# SH_SW20_V1_0.net
KiCad netlist of a schematic drawn in Altium Designer
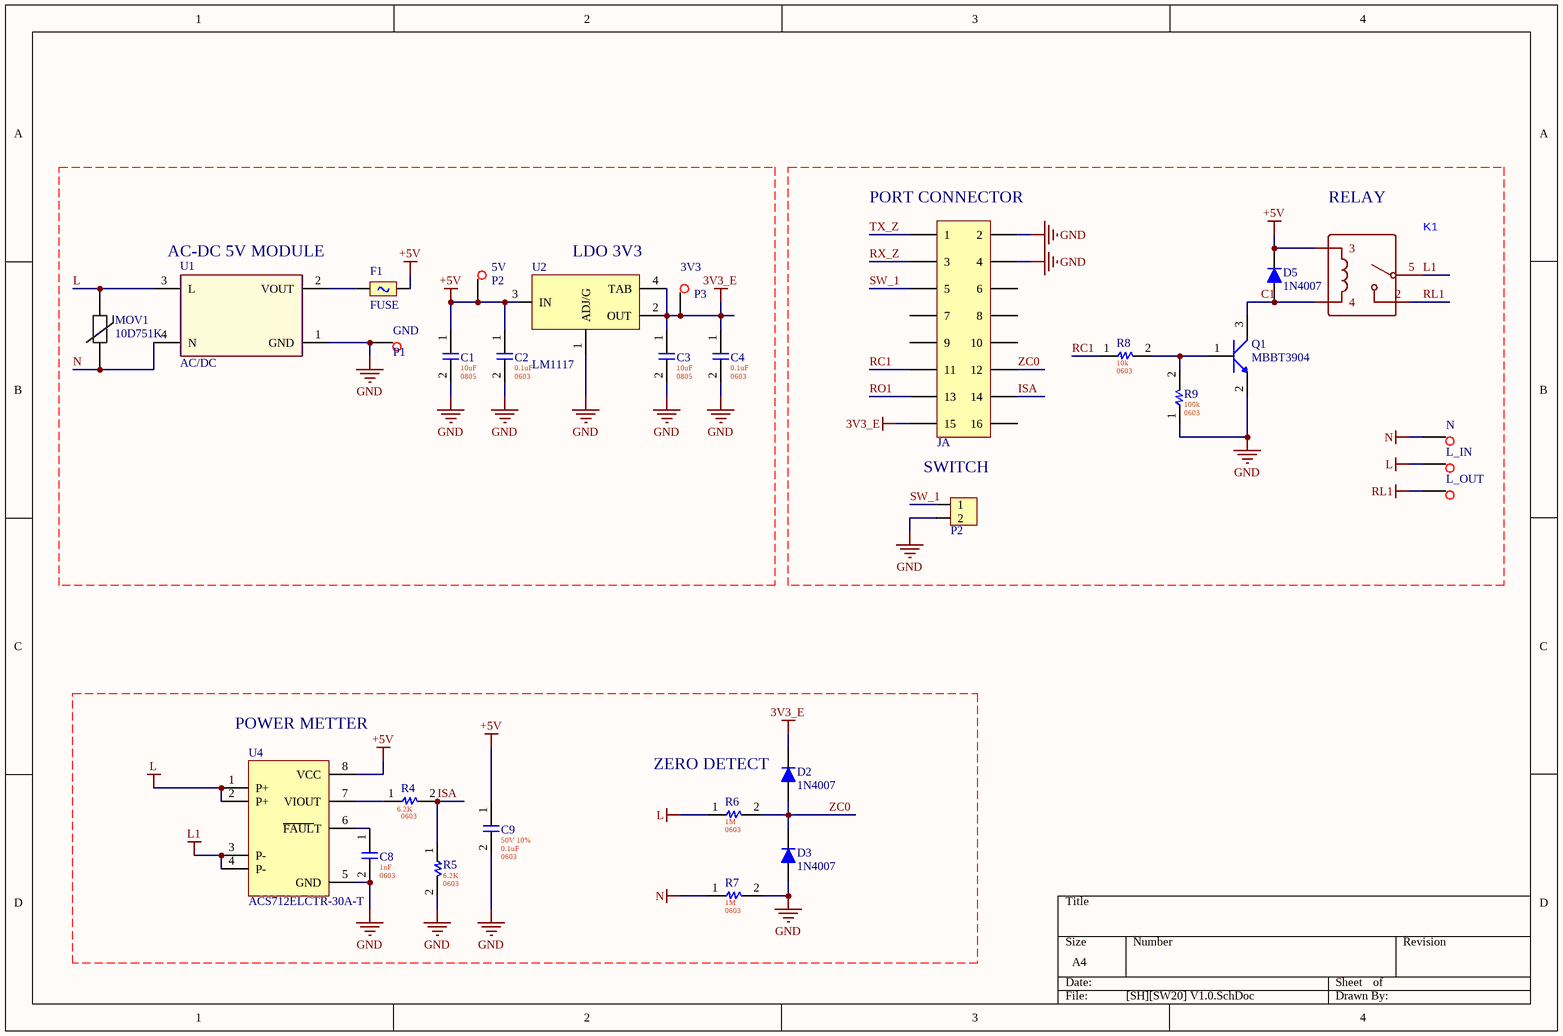
[diagram p0: [SH][SW20] V1.0.SchDoc]

(export (version "E")
  (design (tool "Eeschema 10.0.6"))
  (components
    (comp (ref "3V3") (value "P3") (footprint "TEXT_POINT") (libsource (lib "Kienlib") (part "P1")))
    (comp (ref "5V") (value "P2") (footprint "TEXT_POINT") (libsource (lib "Kienlib") (part "P1")))
    (comp (ref "C1")
      (value "10uF")
      (footprint "0805 C")
      (description "CAP CER 10uF 50V 10% 0805 SMD")
      (fields (field (name "FP") "0805") (field (name "CREATOR") "MMUOP"))
      (libsource (lib "Capacitor") (part "0805 10uF CER"))
    )
    (comp (ref "C2")
      (value "0.1uF")
      (footprint "0603 C")
      (description "CAP CER 0.1uF 50V 10% 0603 SMD")
      (fields (field (name "FP") "0603") (field (name "CREATOR") "MMUOP"))
      (libsource (lib "Capacitor") (part "0603 0.1uF CER"))
    )
    (comp (ref "C3")
      (value "10uF")
      (footprint "0805 C")
      (description "CAP CER 10uF 50V 10% 0805 SMD")
      (fields (field (name "FP") "0805") (field (name "CREATOR") "MMUOP"))
      (libsource (lib "Capacitor") (part "0805 10uF CER"))
    )
    (comp (ref "C4")
      (value "0.1uF")
      (footprint "0603 C")
      (description "CAP CER 0.1uF 50V 10% 0603 SMD")
      (fields (field (name "FP") "0603") (field (name "CREATOR") "MMUOP"))
      (libsource (lib "Capacitor") (part "0603 0.1uF CER"))
    )
    (comp (ref "C8")
      (value "1nF")
      (footprint "0603 C")
      (description "CAP CER 1nF 50V 10% 0603 SMD")
      (fields (field (name "FP") "0603") (field (name "CREATOR") "MMUOP"))
      (libsource (lib "Capacitor") (part "0603 1nF CER"))
    )
    (comp (ref "C9")
      (value "0.1uF")
      (footprint "0603 C")
      (description "CAP CER 0.1uF 50V 10% 0603 SMD")
      (fields
        (field (name "VOLTAGE + TOLE") "50V 10%")
        (field (name "FP") "0603")
        (field (name "CREATOR") "MMUOP")
      )
      (libsource (lib "Capacitor") (part "0603 0.1uF CER"))
    )
    (comp (ref "D2")
      (value "1N4007")
      (footprint "SOD-123")
      (libsource (lib "Kienlib") (part "Diode schottky"))
    )
    (comp (ref "D3")
      (value "1N4007")
      (footprint "SOD-123")
      (libsource (lib "Kienlib") (part "Diode schottky"))
    )
    (comp (ref "D5")
      (value "1N4007")
      (footprint "DO214AC")
      (libsource (lib "Kienlib") (part "Diode schottky"))
    )
    (comp (ref "F1") (value "FUSE") (footprint "1812") (libsource (lib "Kienlib") (part "FUSE")))
    (comp (ref "GND") (value "P1") (footprint "TEXT_POINT") (libsource (lib "Kienlib") (part "P1")))
    (comp (ref "JA")
      (value "rao doi")
      (footprint "P2X8 - 2.0mm - female - SMD")
      (libsource (lib "Kienlib") (part "P2x8"))
    )
    (comp (ref "K1")
      (value "~")
      (footprint "SLA-5VDC-SL-A")
      (description "General Purpose 5VDC SPST-NO Non Latching Through Hole Power Relays ROHS")
      (libsource (lib "altium-import") (part "root_0_SLA-5VDC-SL-A_C688869_"))
    )
    (comp (ref "L_IN") (value "P1") (footprint "P1") (libsource (lib "Kienlib") (part "P1")))
    (comp (ref "L_OUT") (value "P1") (footprint "P1") (libsource (lib "Kienlib") (part "P1")))
    (comp (ref "MOV1")
      (value "10D751K")
      (footprint "MOV")
      (description "750V")
      (libsource (lib "Kienlib") (part "VARISTOR"))
    )
    (comp (ref "N") (value "P1") (footprint "P1") (libsource (lib "Kienlib") (part "P1")))
    (comp (ref "P2") (value "P2") (footprint "P2 - 2.54mm") (libsource (lib "Kienlib") (part "P2")))
    (comp (ref "Q1")
      (value "MBBT3904")
      (footprint "SOT 23-3")
      (description "Bipolar (BJT) Transistor NPN 40 V 200 mA 300MHz 350 mW Surface Mount SOT-23-3 (TO-236)")
      (libsource (lib "Kienlib") (part "TRANS NPN"))
    )
    (comp (ref "R4")
      (value "6.2K")
      (footprint "0603 R")
      (description "8.2k 1% 0603 SMD")
      (fields (field (name "FP") "0603") (field (name "Comment") "8.2k") (field (name "CREATOR") "MMUOP"))
      (libsource (lib "Res") (part "0603 8.2k 1%"))
    )
    (comp (ref "R5")
      (value "6.2K")
      (footprint "0603 R")
      (description "8.2k 1% 0603 SMD")
      (fields (field (name "FP") "0603") (field (name "Comment") "8.2k") (field (name "CREATOR") "MMUOP"))
      (libsource (lib "Res") (part "0603 8.2k 1%"))
    )
    (comp (ref "R6")
      (value "1M")
      (footprint "0603 R")
      (description "1M 1% 0603 SMD")
      (fields (field (name "FP") "0603") (field (name "CREATOR") "MMUOP"))
      (libsource (lib "Res") (part "0603 1M 1%"))
    )
    (comp (ref "R7")
      (value "1M")
      (footprint "0603 R")
      (description "1M 1% 0603 SMD")
      (fields (field (name "FP") "0603") (field (name "CREATOR") "MMUOP"))
      (libsource (lib "Res") (part "0603 1M 1%"))
    )
    (comp (ref "R8")
      (value "10k")
      (footprint "0603 R")
      (description "10k 1% 0603 SMD")
      (fields (field (name "FP") "0603") (field (name "Comment") "10K") (field (name "CREATOR") "MMUOP"))
      (libsource (lib "Res") (part "0603 10k 1%"))
    )
    (comp (ref "R9")
      (value "100k")
      (footprint "0603 R")
      (description "100k 1% 0603 SMD")
      (fields (field (name "FP") "0603") (field (name "CREATOR") "MMUOP"))
      (libsource (lib "Res") (part "0603 100k 1%"))
    )
    (comp (ref "U1") (value "AC/DC") (footprint "AC-DC 5V K4H24") (libsource (lib "Kienlib") (part "AC/DC")))
    (comp (ref "U2") (value "LM1117") (footprint "SOT23-4") (libsource (lib "Kienlib") (part "LM1117")))
    (comp (ref "U4")
      (value "ACS712ELCTR-30A-T")
      (footprint "SOIC 8")
      (description "ACS712ELCTR-20A  SOIC 8")
      (libsource (lib "Kienlib") (part "ACS71240"))
    )
  )
  (nets
    (net (code "1") (name "+5V") (class "Default")
      (node (ref "5V") (pin "1") (pinfunction "P_1") (pintype "passive"))
      (node (ref "C1") (pin "1") (pinfunction "1_1") (pintype "passive"))
      (node (ref "C2") (pin "1") (pinfunction "1_1") (pintype "passive"))
      (node (ref "C9") (pin "1") (pinfunction "1_1") (pintype "passive"))
      (node (ref "D5") (pin "2") (pinfunction "2_2") (pintype "passive"))
      (node (ref "F1") (pin "2") (pinfunction "2_2") (pintype "passive"))
      (node (ref "K1") (pin "3") (pinfunction "3_3") (pintype "passive"))
      (node (ref "U2") (pin "3") (pinfunction "IN_3") (pintype "passive"))
      (node (ref "U4") (pin "8") (pinfunction "VCC_8") (pintype "passive"))
    )
    (net (code "2") (name "/C1") (class "Default")
      (node (ref "D5") (pin "1") (pinfunction "1_1") (pintype "passive"))
      (node (ref "K1") (pin "4") (pinfunction "4_4") (pintype "passive"))
      (node (ref "Q1") (pin "3") (pinfunction "C_3") (pintype "passive"))
    )
    (net (code "3") (name "/ISA") (class "Default")
      (node (ref "JA") (pin "14") (pinfunction "14_14") (pintype "passive"))
      (node (ref "R4") (pin "2") (pinfunction "2_2") (pintype "passive"))
      (node (ref "R5") (pin "1") (pinfunction "1_1") (pintype "passive"))
    )
    (net (code "4") (name "/RC1") (class "Default")
      (node (ref "JA") (pin "11") (pinfunction "11_11") (pintype "passive"))
      (node (ref "R8") (pin "1") (pinfunction "1_1") (pintype "passive"))
    )
    (net (code "5") (name "/RO1") (class "Default")
      (node (ref "JA") (pin "13") (pinfunction "13_13") (pintype "passive"))
    )
    (net (code "6") (name "/RX_Z") (class "Default")
      (node (ref "JA") (pin "3") (pinfunction "3_3") (pintype "passive"))
    )
    (net (code "7") (name "/SW_1") (class "Default")
      (node (ref "JA") (pin "5") (pinfunction "5_5") (pintype "passive"))
      (node (ref "P2") (pin "1") (pinfunction "1_1") (pintype "passive"))
    )
    (net (code "8") (name "/TX_Z") (class "Default")
      (node (ref "JA") (pin "1") (pinfunction "1_1") (pintype "passive"))
    )
    (net (code "9") (name "/ZC0") (class "Default")
      (node (ref "D2") (pin "1") (pinfunction "1_1") (pintype "passive"))
      (node (ref "D3") (pin "2") (pinfunction "2_2") (pintype "passive"))
      (node (ref "JA") (pin "12") (pinfunction "12_12") (pintype "passive"))
      (node (ref "R6") (pin "2") (pinfunction "2_2") (pintype "passive"))
    )
    (net (code "10") (name "3V3_E") (class "Default")
      (node (ref "3V3") (pin "1") (pinfunction "P_1") (pintype "passive"))
      (node (ref "C3") (pin "1") (pinfunction "1_1") (pintype "passive"))
      (node (ref "C4") (pin "1") (pinfunction "1_1") (pintype "passive"))
      (node (ref "D2") (pin "2") (pinfunction "2_2") (pintype "passive"))
      (node (ref "JA") (pin "15") (pinfunction "15_15") (pintype "passive"))
      (node (ref "U2") (pin "2") (pinfunction "OUT_2") (pintype "passive"))
      (node (ref "U2") (pin "4") (pinfunction "TAB_4") (pintype "passive"))
    )
    (net (code "11") (name "GND") (class "Default")
      (node (ref "C1") (pin "2") (pinfunction "2_2") (pintype "passive"))
      (node (ref "C2") (pin "2") (pinfunction "2_2") (pintype "passive"))
      (node (ref "C3") (pin "2") (pinfunction "2_2") (pintype "passive"))
      (node (ref "C4") (pin "2") (pinfunction "2_2") (pintype "passive"))
      (node (ref "C8") (pin "2") (pinfunction "2_2") (pintype "passive"))
      (node (ref "C9") (pin "2") (pinfunction "2_2") (pintype "passive"))
      (node (ref "D3") (pin "1") (pinfunction "1_1") (pintype "passive"))
      (node (ref "GND") (pin "1") (pinfunction "P_1") (pintype "passive"))
      (node (ref "JA") (pin "2") (pinfunction "2_2") (pintype "passive"))
      (node (ref "JA") (pin "4") (pinfunction "4_4") (pintype "passive"))
      (node (ref "P2") (pin "2") (pinfunction "2_2") (pintype "passive"))
      (node (ref "Q1") (pin "2") (pinfunction "E_2") (pintype "passive"))
      (node (ref "R5") (pin "2") (pinfunction "2_2") (pintype "passive"))
      (node (ref "R7") (pin "2") (pinfunction "2_2") (pintype "passive"))
      (node (ref "R9") (pin "1") (pinfunction "1_1") (pintype "passive"))
      (node (ref "U1") (pin "1") (pinfunction "GND_1") (pintype "passive"))
      (node (ref "U2") (pin "1") (pinfunction "ADJ/G_1") (pintype "passive"))
      (node (ref "U4") (pin "5") (pinfunction "GND_5") (pintype "passive"))
    )
    (net (code "12") (name "L") (class "Default")
      (node (ref "L_IN") (pin "1") (pinfunction "P_1") (pintype "passive"))
      (node (ref "MOV1") (pin "2") (pinfunction "2_2") (pintype "passive"))
      (node (ref "R6") (pin "1") (pinfunction "1_1") (pintype "passive"))
      (node (ref "U1") (pin "3") (pinfunction "L_3") (pintype "passive"))
      (node (ref "U4") (pin "1") (pinfunction "P+_1") (pintype "passive"))
      (node (ref "U4") (pin "2") (pinfunction "P+_2") (pintype "passive"))
    )
    (net (code "13") (name "L1") (class "Default")
      (node (ref "K1") (pin "5") (pinfunction "5_5") (pintype "passive"))
      (node (ref "U4") (pin "3") (pinfunction "P-_3") (pintype "passive"))
      (node (ref "U4") (pin "4") (pinfunction "P-_4") (pintype "passive"))
    )
    (net (code "14") (name "N") (class "Default")
      (node (ref "MOV1") (pin "1") (pinfunction "1_1") (pintype "passive"))
      (node (ref "N") (pin "1") (pinfunction "P_1") (pintype "passive"))
      (node (ref "R7") (pin "1") (pinfunction "1_1") (pintype "passive"))
      (node (ref "U1") (pin "4") (pinfunction "N_4") (pintype "passive"))
    )
    (net (code "15") (name "Net-(Q1-B)") (class "Default")
      (node (ref "Q1") (pin "1") (pinfunction "B_1") (pintype "passive"))
      (node (ref "R8") (pin "2") (pinfunction "2_2") (pintype "passive"))
      (node (ref "R9") (pin "2") (pinfunction "2_2") (pintype "passive"))
    )
    (net (code "16") (name "Net-(U1-VOUT)") (class "Default")
      (node (ref "F1") (pin "1") (pinfunction "1_1") (pintype "passive"))
      (node (ref "U1") (pin "2") (pinfunction "VOUT_2") (pintype "passive"))
    )
    (net (code "17") (name "Net-(U4-VIOUT)") (class "Default")
      (node (ref "R4") (pin "1") (pinfunction "1_1") (pintype "passive"))
      (node (ref "U4") (pin "7") (pinfunction "VIOUT_7") (pintype "passive"))
    )
    (net (code "18") (name "Net-(U4-~{FAUL}T)") (class "Default")
      (node (ref "C8") (pin "1") (pinfunction "1_1") (pintype "passive"))
      (node (ref "U4") (pin "6") (pinfunction "~{FAUL}T_6") (pintype "passive"))
    )
    (net (code "19") (name "RL1") (class "Default")
      (node (ref "K1") (pin "2") (pinfunction "2_2") (pintype "passive"))
      (node (ref "L_OUT") (pin "1") (pinfunction "P_1") (pintype "passive"))
    )
    (net (code "20") (name "unconnected-(JA-Pad6)") (class "Default")
      (node (ref "JA") (pin "6") (pinfunction "6_6") (pintype "passive"))
    )
    (net (code "21") (name "unconnected-(JA-Pad7)") (class "Default")
      (node (ref "JA") (pin "7") (pinfunction "7_7") (pintype "passive"))
    )
    (net (code "22") (name "unconnected-(JA-Pad8)") (class "Default")
      (node (ref "JA") (pin "8") (pinfunction "8_8") (pintype "passive"))
    )
    (net (code "23") (name "unconnected-(JA-Pad9)") (class "Default")
      (node (ref "JA") (pin "9") (pinfunction "9_9") (pintype "passive"))
    )
    (net (code "24") (name "unconnected-(JA-Pad10)") (class "Default")
      (node (ref "JA") (pin "10") (pinfunction "10_10") (pintype "passive"))
    )
    (net (code "25") (name "unconnected-(JA-Pad16)") (class "Default")
      (node (ref "JA") (pin "16") (pinfunction "16_16") (pintype "passive"))
    )
  )
)
